# DEBUG_CONN.net
KiCad netlist of a schematic drawn in Altium Designer
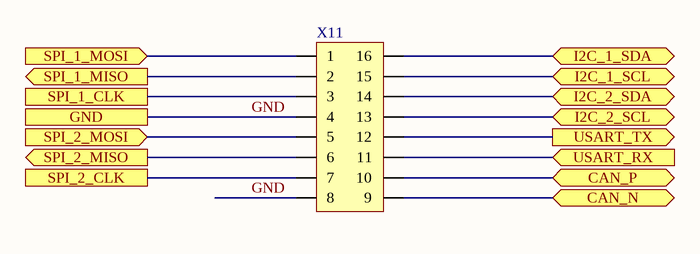
[diagram p0: DEBUG_CONN.SchDoc]

(export (version "E")
  (design (tool "Eeschema 10.0.6"))
  (components
    (comp (ref "X11")
      (value "~")
      (footprint "2x8PinHeader_0.1in")
      (description "Generic 2x8 0.1in pitch pin header")
      (libsource (lib "Connectors") (part "2x8_0.1in"))
    )
  )
  (nets
    (net (code "1") (name "/CAN_N") (class "Default")
      (node (ref "X11") (pin "9") (pinfunction "9_9") (pintype "passive"))
    )
    (net (code "2") (name "/CAN_P") (class "Default")
      (node (ref "X11") (pin "10") (pinfunction "10_10") (pintype "passive"))
    )
    (net (code "3") (name "/GND") (class "Default")
      (node (ref "X11") (pin "4") (pinfunction "4_4") (pintype "passive"))
      (node (ref "X11") (pin "8") (pinfunction "8_8") (pintype "passive"))
    )
    (net (code "4") (name "/I2C_1_SCL") (class "Default")
      (node (ref "X11") (pin "15") (pinfunction "15_15") (pintype "passive"))
    )
    (net (code "5") (name "/I2C_1_SDA") (class "Default")
      (node (ref "X11") (pin "16") (pinfunction "16_16") (pintype "passive"))
    )
    (net (code "6") (name "/I2C_2_SCL") (class "Default")
      (node (ref "X11") (pin "13") (pinfunction "13_13") (pintype "passive"))
    )
    (net (code "7") (name "/I2C_2_SDA") (class "Default")
      (node (ref "X11") (pin "14") (pinfunction "14_14") (pintype "passive"))
    )
    (net (code "8") (name "/SPI_1_CLK") (class "Default")
      (node (ref "X11") (pin "3") (pinfunction "3_3") (pintype "passive"))
    )
    (net (code "9") (name "/SPI_1_MISO") (class "Default")
      (node (ref "X11") (pin "2") (pinfunction "2_2") (pintype "passive"))
    )
    (net (code "10") (name "/SPI_1_MOSI") (class "Default")
      (node (ref "X11") (pin "1") (pinfunction "1_1") (pintype "passive"))
    )
    (net (code "11") (name "/SPI_2_CLK") (class "Default")
      (node (ref "X11") (pin "7") (pinfunction "7_7") (pintype "passive"))
    )
    (net (code "12") (name "/SPI_2_MISO") (class "Default")
      (node (ref "X11") (pin "6") (pinfunction "6_6") (pintype "passive"))
    )
    (net (code "13") (name "/SPI_2_MOSI") (class "Default")
      (node (ref "X11") (pin "5") (pinfunction "5_5") (pintype "passive"))
    )
    (net (code "14") (name "/USART_RX") (class "Default")
      (node (ref "X11") (pin "11") (pinfunction "11_11") (pintype "passive"))
    )
    (net (code "15") (name "/USART_TX") (class "Default")
      (node (ref "X11") (pin "12") (pinfunction "12_12") (pintype "passive"))
    )
  )
)
